# avr002.net
KiCad netlist of a schematic drawn in EAGLE
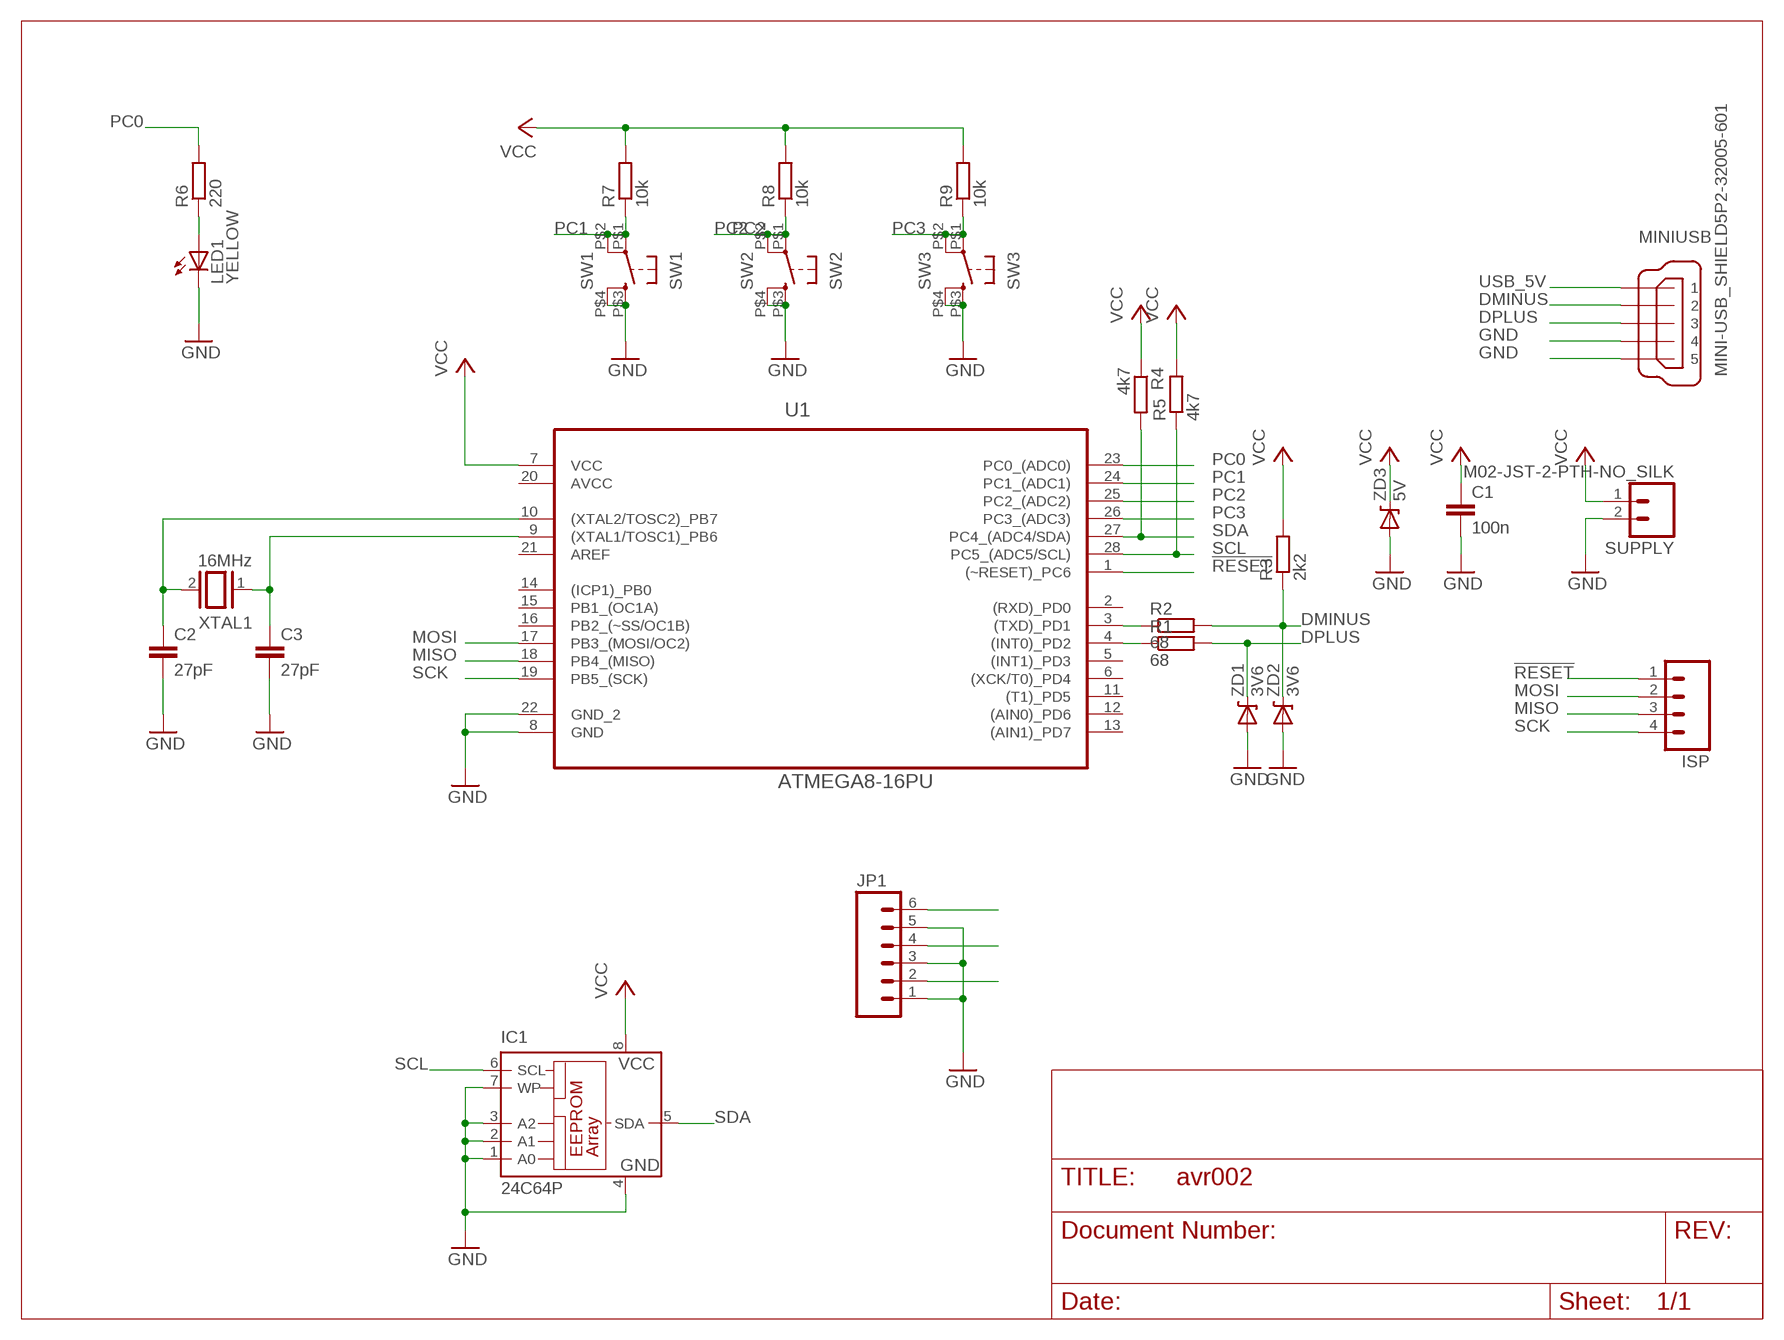
[diagram p0: schematic, sheet 1]

(export (version "E")
  (design (tool "Eeschema 10.0.6"))
  (components
    (comp (ref "C1")
      (value "100n")
      (footprint "eagle-import:C050-024X044")
      (libsource (lib "eagle-import") (part "C-EU050-024X044"))
    )
    (comp (ref "C2")
      (value "27pF")
      (footprint "eagle-import:C050-024X044")
      (libsource (lib "eagle-import") (part "C-EU050-024X044"))
    )
    (comp (ref "C3")
      (value "27pF")
      (footprint "eagle-import:C050-024X044")
      (libsource (lib "eagle-import") (part "C-EU050-024X044"))
    )
    (comp (ref "IC1")
      (value "24C64P")
      (footprint "eagle-import:DIL8")
      (fields (field (name "MF") "RAMTRON INTERNATIONAL CORP") (field (name "MPN") "FM24C64-P"))
      (libsource (lib "eagle-import") (part "24PC64"))
    )
    (comp (ref "ISP")
      (value "M04POLAR")
      (footprint "eagle-import:MOLEX-1X4")
      (libsource (lib "eagle-import") (part "M04POLAR"))
    )
    (comp (ref "JP1")
      (value "M06POLAR")
      (footprint "eagle-import:MOLEX-1X6")
      (libsource (lib "eagle-import") (part "M06POLAR"))
    )
    (comp (ref "LED1")
      (value "YELLOW")
      (footprint "eagle-import:LED5MM")
      (libsource (lib "eagle-import") (part "LED5MM"))
    )
    (comp (ref "MINIUSB")
      (value "MINI-USB_SHIELD5P2-32005-601")
      (footprint "eagle-import:32005-601")
      (libsource (lib "eagle-import") (part "MINI-USB_SHIELD5P2-32005-601"))
    )
    (comp (ref "R1")
      (value "68")
      (footprint "eagle-import:0204_7")
      (libsource (lib "eagle-import") (part "R-EU_0204/7"))
    )
    (comp (ref "R2")
      (value "68")
      (footprint "eagle-import:0204_7")
      (libsource (lib "eagle-import") (part "R-EU_0204/7"))
    )
    (comp (ref "R3")
      (value "2k2")
      (footprint "eagle-import:0204_7")
      (libsource (lib "eagle-import") (part "R-EU_0204/7"))
    )
    (comp (ref "R4")
      (value "4k7")
      (footprint "eagle-import:0204_7")
      (libsource (lib "eagle-import") (part "R-EU_0204/7"))
    )
    (comp (ref "R5")
      (value "4k7")
      (footprint "eagle-import:0204_7")
      (libsource (lib "eagle-import") (part "R-EU_0204/7"))
    )
    (comp (ref "R6")
      (value "220")
      (footprint "eagle-import:0204_7")
      (libsource (lib "eagle-import") (part "R-EU_0204/7"))
    )
    (comp (ref "R7")
      (value "10k")
      (footprint "eagle-import:0204_7")
      (libsource (lib "eagle-import") (part "R-EU_0204/7"))
    )
    (comp (ref "R8")
      (value "10k")
      (footprint "eagle-import:0204_7")
      (libsource (lib "eagle-import") (part "R-EU_0204/7"))
    )
    (comp (ref "R9")
      (value "10k")
      (footprint "eagle-import:0204_7")
      (libsource (lib "eagle-import") (part "R-EU_0204/7"))
    )
    (comp (ref "SUPPLY")
      (value "M02-JST-2-PTH-NO_SILK")
      (footprint "eagle-import:JST-2-PTH-NS")
      (libsource (lib "eagle-import") (part "M02-JST-2-PTH-NO_SILK"))
    )
    (comp (ref "SW1")
      (value "SW1")
      (footprint "eagle-import:KSA_SEALED_TAC_SWITCH")
      (libsource (lib "eagle-import") (part "TAC_SWITCHKSA_SEALED"))
    )
    (comp (ref "SW2")
      (value "SW2")
      (footprint "eagle-import:KSA_SEALED_TAC_SWITCH")
      (libsource (lib "eagle-import") (part "TAC_SWITCHKSA_SEALED"))
    )
    (comp (ref "SW3")
      (value "SW3")
      (footprint "eagle-import:KSA_SEALED_TAC_SWITCH")
      (libsource (lib "eagle-import") (part "TAC_SWITCHKSA_SEALED"))
    )
    (comp (ref "U1")
      (value "ATMEGA8-16PU")
      (footprint "eagle-import:DIP254P762X457-28")
      (libsource (lib "eagle-import") (part "ATMEGA8-16PU"))
    )
    (comp (ref "XTAL1")
      (value "16MHz")
      (footprint "eagle-import:Q")
      (libsource (lib "eagle-import") (part "XTAL"))
    )
    (comp (ref "ZD1")
      (value "3V6")
      (footprint "eagle-import:DIODE-ZENER")
      (libsource (lib "eagle-import") (part "DIODE-ZENERPTH"))
    )
    (comp (ref "ZD2")
      (value "3V6")
      (footprint "eagle-import:DIODE-ZENER")
      (libsource (lib "eagle-import") (part "DIODE-ZENERPTH"))
    )
    (comp (ref "ZD3")
      (value "5V")
      (footprint "eagle-import:DIODE-ZENER")
      (libsource (lib "eagle-import") (part "DIODE-ZENERPTH"))
    )
  )
  (nets
    (net (code "1") (name "/AVCC") (class "Default")
      (node (ref "U1") (pin "20") (pinfunction "AVCC_20") (pintype "power_in"))
    )
    (net (code "2") (name "/DMINUS") (class "Default")
      (node (ref "MINIUSB") (pin "2") (pinfunction "2_2") (pintype "passive"))
      (node (ref "R2") (pin "2") (pinfunction "2_2") (pintype "passive"))
      (node (ref "R3") (pin "1") (pinfunction "1_1") (pintype "passive"))
      (node (ref "ZD2") (pin "P$1") (pinfunction "C_P$1") (pintype "passive"))
    )
    (net (code "3") (name "/DPLUS") (class "Default")
      (node (ref "MINIUSB") (pin "3") (pinfunction "3_3") (pintype "passive"))
      (node (ref "R1") (pin "2") (pinfunction "2_2") (pintype "passive"))
      (node (ref "ZD1") (pin "P$1") (pinfunction "C_P$1") (pintype "passive"))
    )
    (net (code "4") (name "/MISO") (class "Default")
      (node (ref "ISP") (pin "3") (pinfunction "3_3") (pintype "passive"))
      (node (ref "U1") (pin "18") (pinfunction "PB4_(MISO)_18") (pintype "bidirectional"))
    )
    (net (code "5") (name "/MOSI") (class "Default")
      (node (ref "ISP") (pin "2") (pinfunction "2_2") (pintype "passive"))
      (node (ref "U1") (pin "17") (pinfunction "PB3_(MOSI/OC2)_17") (pintype "bidirectional"))
    )
    (net (code "6") (name "/PC0") (class "Default")
      (node (ref "R6") (pin "2") (pinfunction "2_2") (pintype "passive"))
      (node (ref "U1") (pin "23") (pinfunction "PC0_(ADC0)_23") (pintype "bidirectional"))
    )
    (net (code "7") (name "/PC1") (class "Default")
      (node (ref "JP1") (pin "2") (pinfunction "2_2") (pintype "passive"))
      (node (ref "R7") (pin "1") (pinfunction "1_1") (pintype "passive"))
      (node (ref "SW1") (pin "P$1") (pinfunction "1_P$1") (pintype "passive"))
      (node (ref "SW1") (pin "P$2") (pinfunction "2_P$2") (pintype "passive"))
      (node (ref "U1") (pin "24") (pinfunction "PC1_(ADC1)_24") (pintype "bidirectional"))
    )
    (net (code "8") (name "/PC2") (class "Default")
      (node (ref "JP1") (pin "4") (pinfunction "4_4") (pintype "passive"))
      (node (ref "R8") (pin "1") (pinfunction "1_1") (pintype "passive"))
      (node (ref "SW2") (pin "P$1") (pinfunction "1_P$1") (pintype "passive"))
      (node (ref "SW2") (pin "P$2") (pinfunction "2_P$2") (pintype "passive"))
      (node (ref "U1") (pin "25") (pinfunction "PC2_(ADC2)_25") (pintype "bidirectional"))
    )
    (net (code "9") (name "/PC3") (class "Default")
      (node (ref "JP1") (pin "6") (pinfunction "6_6") (pintype "passive"))
      (node (ref "R9") (pin "1") (pinfunction "1_1") (pintype "passive"))
      (node (ref "SW3") (pin "P$1") (pinfunction "1_P$1") (pintype "passive"))
      (node (ref "SW3") (pin "P$2") (pinfunction "2_P$2") (pintype "passive"))
      (node (ref "U1") (pin "26") (pinfunction "PC3_(ADC3)_26") (pintype "bidirectional"))
    )
    (net (code "10") (name "/SCK") (class "Default")
      (node (ref "ISP") (pin "4") (pinfunction "4_4") (pintype "passive"))
      (node (ref "U1") (pin "19") (pinfunction "PB5_(SCK)_19") (pintype "bidirectional"))
    )
    (net (code "11") (name "/SCL") (class "Default")
      (node (ref "IC1") (pin "6") (pinfunction "SCL_6") (pintype "input"))
      (node (ref "R5") (pin "1") (pinfunction "1_1") (pintype "passive"))
      (node (ref "U1") (pin "28") (pinfunction "PC5_(ADC5/SCL)_28") (pintype "bidirectional"))
    )
    (net (code "12") (name "/SDA") (class "Default")
      (node (ref "IC1") (pin "5") (pinfunction "SDA_5") (pintype "bidirectional"))
      (node (ref "R4") (pin "2") (pinfunction "2_2") (pintype "passive"))
      (node (ref "U1") (pin "27") (pinfunction "PC4_(ADC4/SDA)_27") (pintype "bidirectional"))
    )
    (net (code "13") (name "/USB_5V") (class "Default")
      (node (ref "MINIUSB") (pin "1") (pinfunction "1_1") (pintype "passive"))
    )
    (net (code "14") (name "/~{RESET}") (class "Default")
      (node (ref "ISP") (pin "1") (pinfunction "1_1") (pintype "passive"))
      (node (ref "U1") (pin "1") (pinfunction "(~{RESET})_PC6_1") (pintype "bidirectional"))
    )
    (net (code "15") (name "GND") (class "Default")
      (node (ref "C1") (pin "2") (pinfunction "2_2") (pintype "passive"))
      (node (ref "C2") (pin "2") (pinfunction "2_2") (pintype "passive"))
      (node (ref "C3") (pin "2") (pinfunction "2_2") (pintype "passive"))
      (node (ref "IC1") (pin "1") (pinfunction "A0_1") (pintype "input"))
      (node (ref "IC1") (pin "2") (pinfunction "A1_2") (pintype "input"))
      (node (ref "IC1") (pin "3") (pinfunction "A2_3") (pintype "input"))
      (node (ref "IC1") (pin "4") (pinfunction "GND_4") (pintype "power_in"))
      (node (ref "IC1") (pin "7") (pinfunction "WP_7") (pintype "input"))
      (node (ref "JP1") (pin "1") (pinfunction "1_1") (pintype "passive"))
      (node (ref "JP1") (pin "3") (pinfunction "3_3") (pintype "passive"))
      (node (ref "JP1") (pin "5") (pinfunction "5_5") (pintype "passive"))
      (node (ref "LED1") (pin "K") (pinfunction "C_K") (pintype "passive"))
      (node (ref "MINIUSB") (pin "4") (pinfunction "4_4") (pintype "passive"))
      (node (ref "MINIUSB") (pin "5") (pinfunction "5_5") (pintype "passive"))
      (node (ref "SUPPLY") (pin "2") (pinfunction "2_2") (pintype "passive"))
      (node (ref "SW1") (pin "P$3") (pinfunction "3_P$3") (pintype "passive"))
      (node (ref "SW1") (pin "P$4") (pinfunction "4_P$4") (pintype "passive"))
      (node (ref "SW2") (pin "P$3") (pinfunction "3_P$3") (pintype "passive"))
      (node (ref "SW2") (pin "P$4") (pinfunction "4_P$4") (pintype "passive"))
      (node (ref "SW3") (pin "P$3") (pinfunction "3_P$3") (pintype "passive"))
      (node (ref "SW3") (pin "P$4") (pinfunction "4_P$4") (pintype "passive"))
      (node (ref "U1") (pin "22") (pinfunction "GND_2_22") (pintype "passive"))
      (node (ref "U1") (pin "8") (pinfunction "GND_8") (pintype "passive"))
      (node (ref "ZD1") (pin "P$2") (pinfunction "A_P$2") (pintype "passive"))
      (node (ref "ZD2") (pin "P$2") (pinfunction "A_P$2") (pintype "passive"))
      (node (ref "ZD3") (pin "P$2") (pinfunction "A_P$2") (pintype "passive"))
    )
    (net (code "16") (name "Net-(LED1-PadA)") (class "Default")
      (node (ref "LED1") (pin "A") (pinfunction "A_A") (pintype "passive"))
      (node (ref "R6") (pin "1") (pinfunction "1_1") (pintype "passive"))
    )
    (net (code "17") (name "Net-(U1-(INT0)_PD2)") (class "Default")
      (node (ref "R1") (pin "1") (pinfunction "1_1") (pintype "passive"))
      (node (ref "U1") (pin "4") (pinfunction "(INT0)_PD2_4") (pintype "bidirectional"))
    )
    (net (code "18") (name "Net-(U1-(TXD)_PD1)") (class "Default")
      (node (ref "R2") (pin "1") (pinfunction "1_1") (pintype "passive"))
      (node (ref "U1") (pin "3") (pinfunction "(TXD)_PD1_3") (pintype "bidirectional"))
    )
    (net (code "19") (name "Net-(U1-(XTAL1{slash}TOSC1)_PB6)") (class "Default")
      (node (ref "C3") (pin "1") (pinfunction "1_1") (pintype "passive"))
      (node (ref "U1") (pin "9") (pinfunction "(XTAL1/TOSC1)_PB6_9") (pintype "input"))
      (node (ref "XTAL1") (pin "1") (pinfunction "1_1") (pintype "passive"))
    )
    (net (code "20") (name "Net-(U1-(XTAL2{slash}TOSC2)_PB7)") (class "Default")
      (node (ref "C2") (pin "1") (pinfunction "1_1") (pintype "passive"))
      (node (ref "U1") (pin "10") (pinfunction "(XTAL2/TOSC2)_PB7_10") (pintype "input"))
      (node (ref "XTAL1") (pin "2") (pinfunction "2_2") (pintype "passive"))
    )
    (net (code "21") (name "VCC") (class "Default")
      (node (ref "C1") (pin "1") (pinfunction "1_1") (pintype "passive"))
      (node (ref "IC1") (pin "8") (pinfunction "VCC_8") (pintype "power_in"))
      (node (ref "R3") (pin "2") (pinfunction "2_2") (pintype "passive"))
      (node (ref "R4") (pin "1") (pinfunction "1_1") (pintype "passive"))
      (node (ref "R5") (pin "2") (pinfunction "2_2") (pintype "passive"))
      (node (ref "R7") (pin "2") (pinfunction "2_2") (pintype "passive"))
      (node (ref "R8") (pin "2") (pinfunction "2_2") (pintype "passive"))
      (node (ref "R9") (pin "2") (pinfunction "2_2") (pintype "passive"))
      (node (ref "SUPPLY") (pin "1") (pinfunction "1_1") (pintype "passive"))
      (node (ref "U1") (pin "7") (pinfunction "VCC_7") (pintype "power_in"))
      (node (ref "ZD3") (pin "P$1") (pinfunction "C_P$1") (pintype "passive"))
    )
    (net (code "22") (name "unconnected-(U1-(AIN0)_PD6-Pad12)") (class "Default")
      (node (ref "U1") (pin "12") (pinfunction "(AIN0)_PD6_12") (pintype "bidirectional"))
    )
    (net (code "23") (name "unconnected-(U1-(AIN1)_PD7-Pad13)") (class "Default")
      (node (ref "U1") (pin "13") (pinfunction "(AIN1)_PD7_13") (pintype "bidirectional"))
    )
    (net (code "24") (name "unconnected-(U1-(ICP1)_PB0-Pad14)") (class "Default")
      (node (ref "U1") (pin "14") (pinfunction "(ICP1)_PB0_14") (pintype "bidirectional"))
    )
    (net (code "25") (name "unconnected-(U1-(INT1)_PD3-Pad5)") (class "Default")
      (node (ref "U1") (pin "5") (pinfunction "(INT1)_PD3_5") (pintype "bidirectional"))
    )
    (net (code "26") (name "unconnected-(U1-(RXD)_PD0-Pad2)") (class "Default")
      (node (ref "U1") (pin "2") (pinfunction "(RXD)_PD0_2") (pintype "bidirectional"))
    )
    (net (code "27") (name "unconnected-(U1-(T1)_PD5-Pad11)") (class "Default")
      (node (ref "U1") (pin "11") (pinfunction "(T1)_PD5_11") (pintype "bidirectional"))
    )
    (net (code "28") (name "unconnected-(U1-(XCK{slash}T0)_PD4-Pad6)") (class "Default")
      (node (ref "U1") (pin "6") (pinfunction "(XCK/T0)_PD4_6") (pintype "bidirectional"))
    )
    (net (code "29") (name "unconnected-(U1-AREF-Pad21)") (class "Default")
      (node (ref "U1") (pin "21") (pinfunction "AREF_21") (pintype "input"))
    )
    (net (code "30") (name "unconnected-(U1-PB1_(OC1A)-Pad15)") (class "Default")
      (node (ref "U1") (pin "15") (pinfunction "PB1_(OC1A)_15") (pintype "bidirectional"))
    )
    (net (code "31") (name "unconnected-(U1-PB2_(~{SS{slash}OC1B})-Pad16)") (class "Default")
      (node (ref "U1") (pin "16") (pinfunction "PB2_(~{SS/OC1B})_16") (pintype "bidirectional"))
    )
  )
)
